# 15V_fire.net
KiCad netlist of a schematic drawn in Altium Designer
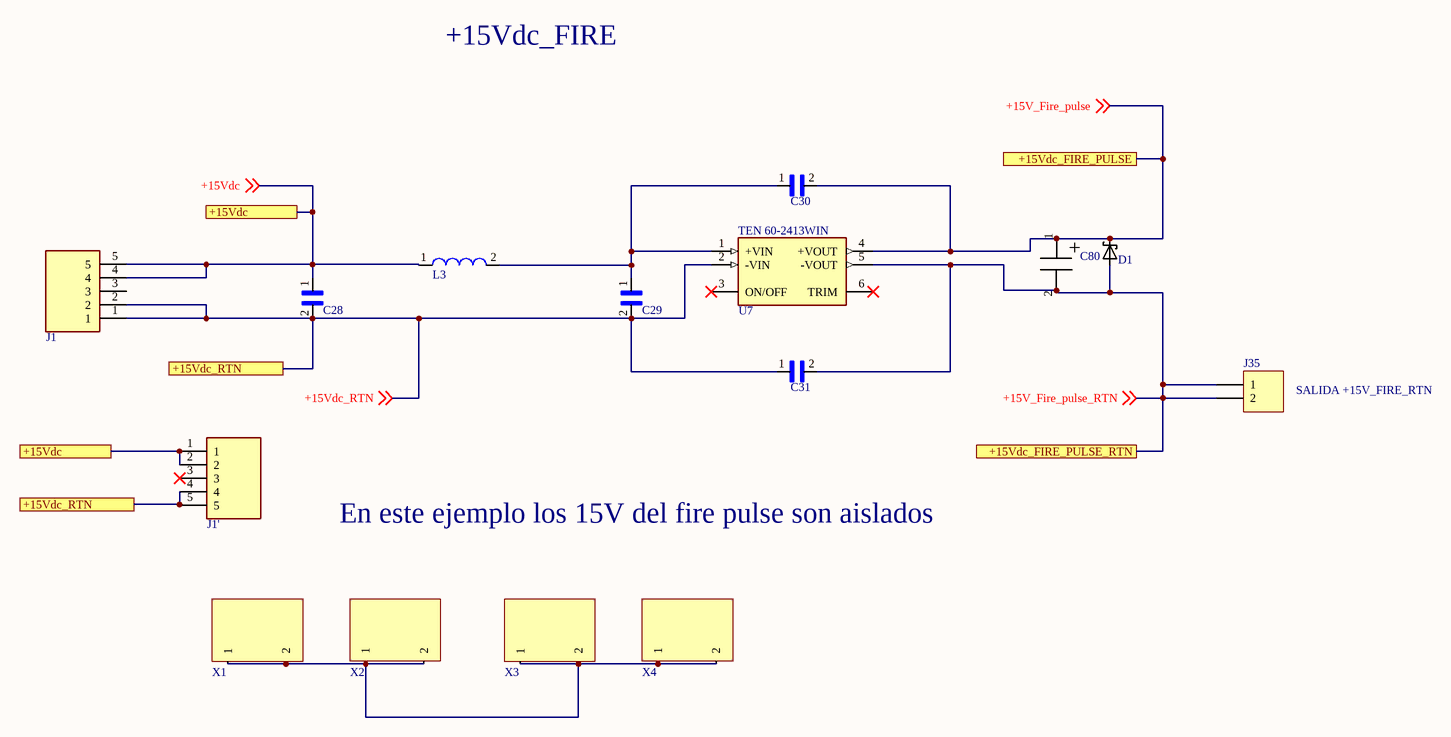
[diagram p0: +15V_fire.SchDoc]

(export (version "E")
  (design (tool "Eeschema 10.0.6"))
  (components
    (comp (ref "C28")
      (value "KTF500B685M43NHT00")
      (footprint "MLCC SMD 1812 50V")
      (description "6.8uF, 50V")
      (libsource (lib "Schlib1") (part "MLCC - SMD 1812"))
    )
    (comp (ref "C29")
      (value "KTF500B685M43NHT00")
      (footprint "MLCC SMD 1812 50V")
      (description "6.8uF, 50V")
      (libsource (lib "Schlib1") (part "MLCC - SMD 1812"))
    )
    (comp (ref "C30")
      (value "C1206X102KGRACAUTO")
      (footprint "MLCC SMD 1206")
      (description "1000Pf, 2KV")
      (libsource (lib "Schlib1") (part "MLCC - SMD 1206"))
    )
    (comp (ref "C31")
      (value "C1206X102KGRACAUTO")
      (footprint "MLCC SMD 1206")
      (description "1000Pf, 2KV")
      (libsource (lib "Schlib1") (part "MLCC - SMD 1206"))
    )
    (comp (ref "C80")
      (value "EEE-FK1V100R")
      (footprint "PANASONIC FK SERIES")
      (description "10uF, 35V")
      (libsource (lib "Schlib1") (part "Panasonic electrolitic cap FK"))
    )
    (comp (ref "D1")
      (value "SMCJ15A")
      (footprint "TVS Diode DO-214AB-2 (SMC)")
      (description "SMC do-214AB-2")
      (libsource (lib "Schlib1") (part "TVS SMCJxxA"))
    )
    (comp (ref "J1")
      (value "Pin Header 5x1 MASC")
      (footprint "PIN HEADER 5X1 MASC")
      (description "5x1 Straight MASC")
      (libsource (lib "Schlib1") (part "Pin Header 5x1 MASC"))
    )
    (comp (ref "J1'")
      (value "Pin Header 5x1 MASC")
      (footprint "PIN HEADER 5X1 MASC")
      (description "5x1 Straight MASC")
      (libsource (lib "") (part "Pin Header 5x1 MASC_1"))
    )
    (comp (ref "J35")
      (value "Header 2")
      (footprint "HDR1X2")
      (description "Header, 2-Pin")
      (fields (field (name "PUBLISHER") "Altium Limited"))
      (libsource (lib "Miscellaneous Connectors") (part "Header 2"))
    )
    (comp (ref "L3")
      (value "TCK-102")
      (footprint "TCK-102")
      (description "Inductores fijos EMC Chokes for DC/DC Converters 3.3 µH ±20% 18 mOhm max. 10Amax")
      (libsource (lib "Schlib1") (part "TCK-102"))
    )
    (comp (ref "U7")
      (value "TEN 60-2413WIN")
      (footprint "TEN 60WIN Series")
      (description "Convertidores CC/CC aislados  Output Power (W): 60; Input Voltage: 9-36 VDC; Output 1 (Vdc): 15;")
      (libsource (lib "Schlib1") (part "TEN 60-2413WIN"))
    )
    (comp (ref "X1")
      (value "7466310R")
      (footprint "7466310R")
      (libsource (lib "") (part "7466310R Conector_1"))
    )
    (comp (ref "X2")
      (value "7466310R")
      (footprint "7466310R")
      (libsource (lib "Schlib1") (part "7466310R Conector"))
    )
    (comp (ref "X3")
      (value "7466310R")
      (footprint "7466310R")
      (libsource (lib "") (part "7466310R Conector_1"))
    )
    (comp (ref "X4")
      (value "7466310R")
      (footprint "7466310R")
      (libsource (lib "Schlib1") (part "7466310R Conector"))
    )
  )
  (nets
    (net (code "1") (name "+15V_Fire_pulse") (class "Default")
      (node (ref "C30") (pin "2") (pinfunction "2_2") (pintype "passive"))
      (node (ref "C80") (pin "1") (pintype "passive"))
      (node (ref "D1") (pin "C") (pinfunction "C_C") (pintype "passive"))
      (node (ref "U7") (pin "4") (pinfunction "+VOUT_4") (pintype "output"))
    )
    (net (code "2") (name "+15V_Fire_pulse_RTN") (class "Default")
      (node (ref "C31") (pin "2") (pinfunction "2_2") (pintype "passive"))
      (node (ref "C80") (pin "2") (pintype "passive"))
      (node (ref "D1") (pin "A") (pinfunction "1_A") (pintype "passive"))
      (node (ref "J35") (pin "1") (pinfunction "1_1") (pintype "passive"))
      (node (ref "J35") (pin "2") (pinfunction "2_2") (pintype "passive"))
      (node (ref "U7") (pin "5") (pinfunction "-VOUT_5") (pintype "output"))
    )
    (net (code "3") (name "+15Vdc") (class "Default")
      (node (ref "C28") (pin "1") (pinfunction "1_1") (pintype "passive"))
      (node (ref "J1") (pin "4") (pinfunction "4_4") (pintype "passive"))
      (node (ref "J1") (pin "5") (pinfunction "5_5") (pintype "passive"))
      (node (ref "J1'") (pin "1") (pinfunction "1_1") (pintype "passive"))
      (node (ref "J1'") (pin "2") (pinfunction "2_2") (pintype "passive"))
      (node (ref "L3") (pin "1") (pinfunction "1_1") (pintype "passive"))
    )
    (net (code "4") (name "+15Vdc_RTN") (class "Default")
      (node (ref "C28") (pin "2") (pinfunction "2_2") (pintype "passive"))
      (node (ref "C29") (pin "2") (pinfunction "2_2") (pintype "passive"))
      (node (ref "C31") (pin "1") (pinfunction "1_1") (pintype "passive"))
      (node (ref "J1") (pin "1") (pinfunction "1_1") (pintype "passive"))
      (node (ref "J1") (pin "2") (pinfunction "2_2") (pintype "passive"))
      (node (ref "J1'") (pin "4") (pinfunction "4_4") (pintype "passive"))
      (node (ref "J1'") (pin "5") (pinfunction "5_5") (pintype "passive"))
      (node (ref "U7") (pin "2") (pinfunction "-VIN_2") (pintype "input"))
    )
    (net (code "5") (name "Net-(U7-+VIN)") (class "Default")
      (node (ref "C29") (pin "1") (pinfunction "1_1") (pintype "passive"))
      (node (ref "C30") (pin "1") (pinfunction "1_1") (pintype "passive"))
      (node (ref "L3") (pin "2") (pinfunction "2_2") (pintype "passive"))
      (node (ref "U7") (pin "1") (pinfunction "+VIN_1") (pintype "input"))
    )
    (net (code "6") (name "Net-(X1-Pad1)") (class "Default")
      (node (ref "X1") (pin "1") (pinfunction "1_1") (pintype "passive"))
      (node (ref "X1") (pin "2") (pinfunction "2_2") (pintype "passive"))
      (node (ref "X2") (pin "1") (pinfunction "1_1") (pintype "passive"))
      (node (ref "X2") (pin "2") (pinfunction "2_2") (pintype "passive"))
      (node (ref "X3") (pin "1") (pinfunction "1_1") (pintype "passive"))
      (node (ref "X3") (pin "2") (pinfunction "2_2") (pintype "passive"))
      (node (ref "X4") (pin "1") (pinfunction "1_1") (pintype "passive"))
      (node (ref "X4") (pin "2") (pinfunction "2_2") (pintype "passive"))
    )
    (net (code "7") (name "unconnected-(J1'-Pad3)") (class "Default")
      (node (ref "J1'") (pin "3") (pinfunction "3_3") (pintype "passive+no_connect"))
    )
    (net (code "8") (name "unconnected-(J1-Pad3)") (class "Default")
      (node (ref "J1") (pin "3") (pinfunction "3_3") (pintype "passive"))
    )
    (net (code "9") (name "unconnected-(U7-ON{slash}OFF-Pad3)") (class "Default")
      (node (ref "U7") (pin "3") (pinfunction "ON/OFF_3") (pintype "passive+no_connect"))
    )
    (net (code "10") (name "unconnected-(U7-TRIM-Pad6)") (class "Default")
      (node (ref "U7") (pin "6") (pinfunction "TRIM_6") (pintype "passive+no_connect"))
    )
  )
)
